# pc_sensything_v1_6.net
KiCad netlist of a schematic drawn in EAGLE
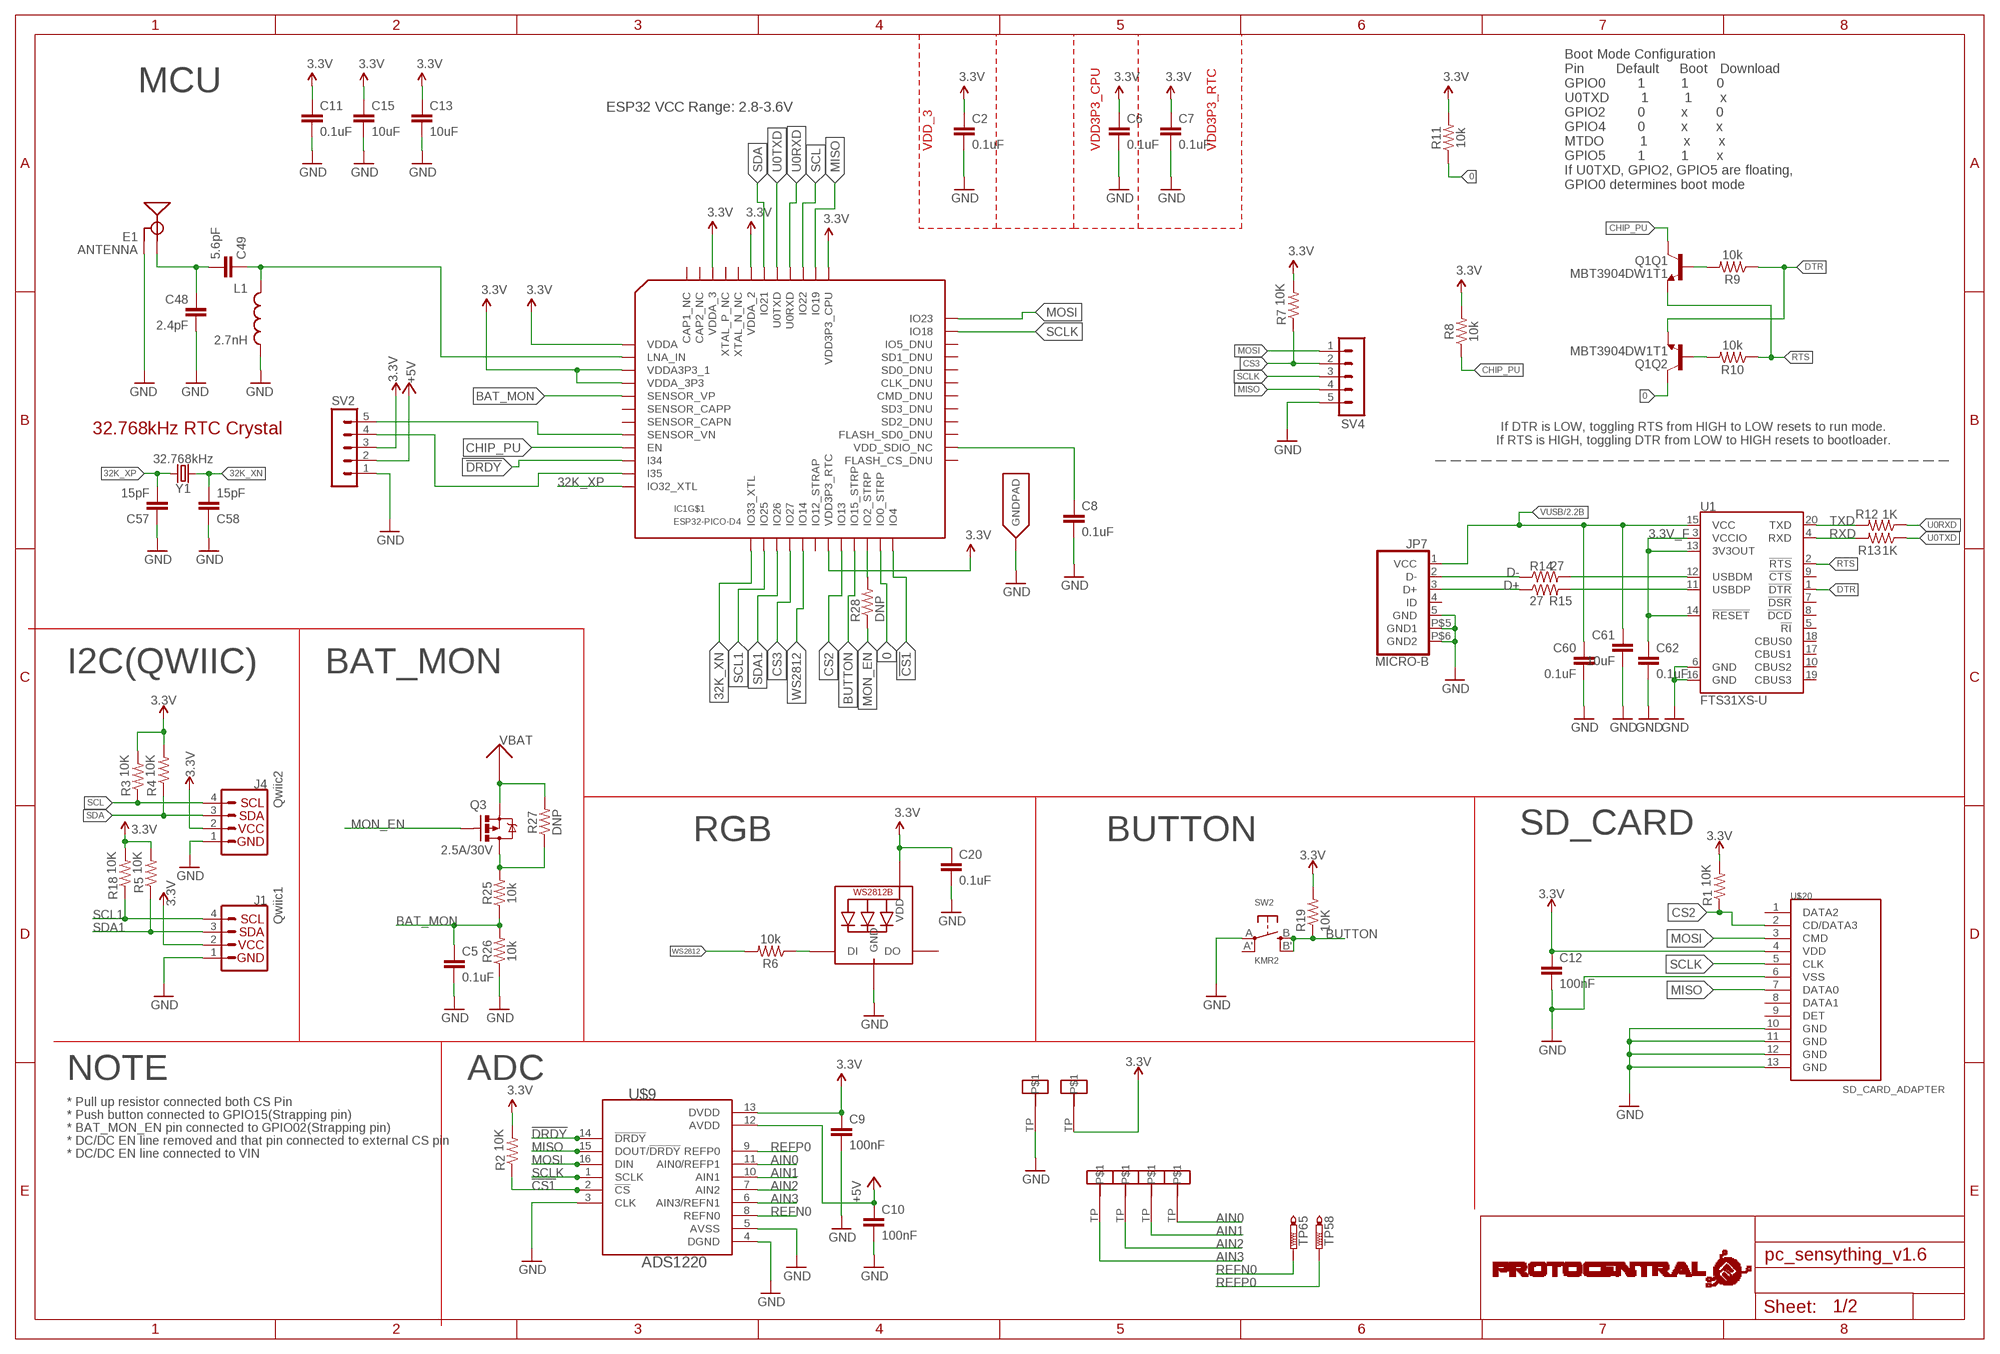
[diagram p0: schematic, sheet 1]
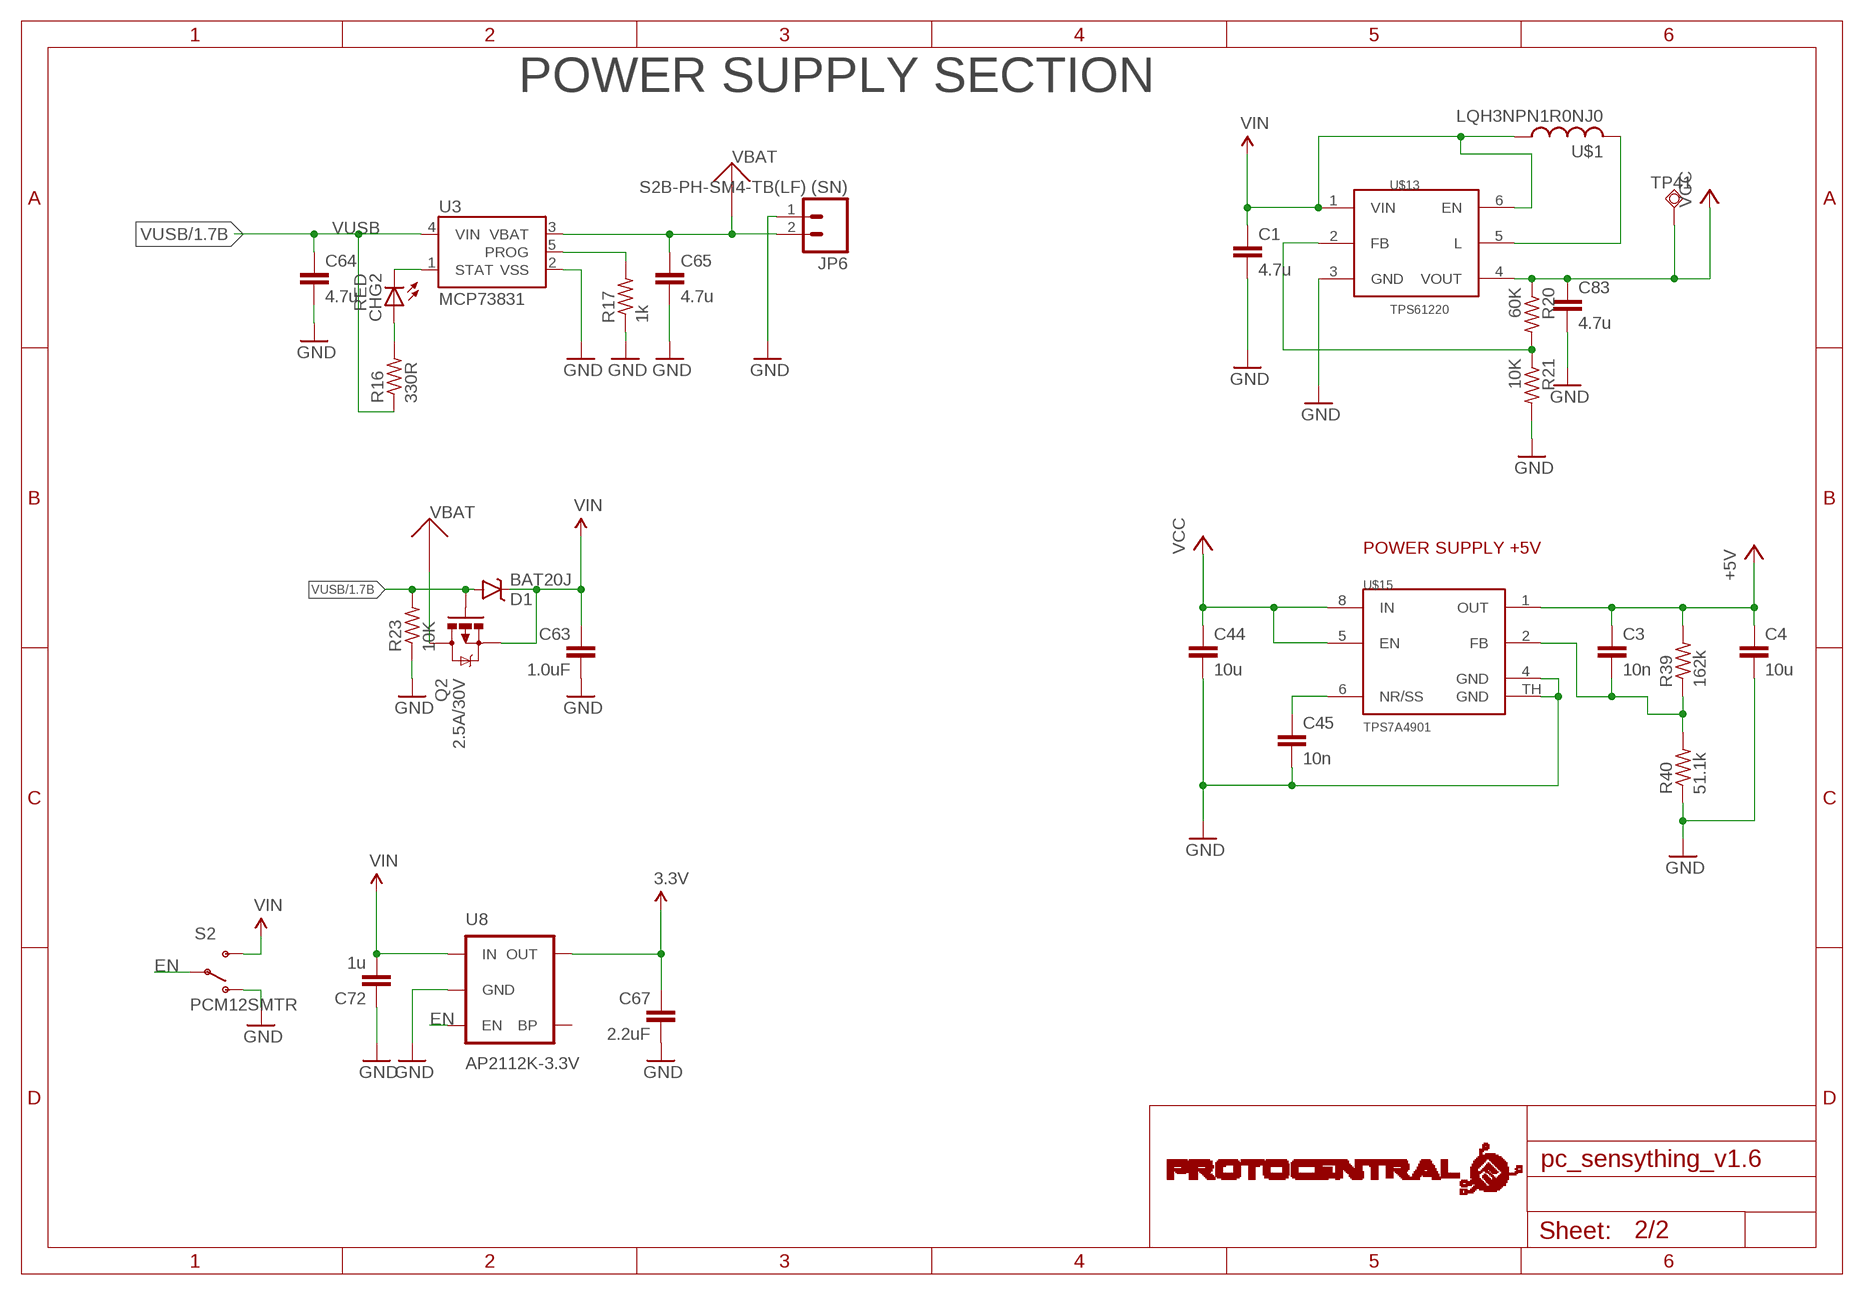
[diagram p1: schematic, sheet 2]

(export (version "E")
  (design (tool "Eeschema 10.0.6"))
  (components
    (comp (ref "C1")
      (value "4.7u")
      (footprint "eagle-import:C0805")
      (libsource (lib "eagle-import") (part "C-EUC0805"))
    )
    (comp (ref "C3")
      (value "10n")
      (footprint "eagle-import:C0402")
      (libsource (lib "eagle-import") (part "C-EUC0402"))
    )
    (comp (ref "C4")
      (value "10u")
      (footprint "eagle-import:C0805")
      (libsource (lib "eagle-import") (part "C-EUC0805"))
    )
    (comp (ref "C44")
      (value "10u")
      (footprint "eagle-import:C0805")
      (libsource (lib "eagle-import") (part "C-EUC0805"))
    )
    (comp (ref "C45")
      (value "10n")
      (footprint "eagle-import:C0402")
      (libsource (lib "eagle-import") (part "C-EUC0402"))
    )
    (comp (ref "C63")
      (value "1.0uF")
      (footprint "eagle-import:C0402")
      (libsource (lib "eagle-import") (part "C-EUC0402"))
    )
    (comp (ref "C64")
      (value "4.7u")
      (footprint "eagle-import:C0805")
      (libsource (lib "eagle-import") (part "C-EUC0805"))
    )
    (comp (ref "C65")
      (value "4.7u")
      (footprint "eagle-import:C0805")
      (libsource (lib "eagle-import") (part "C-EUC0805"))
    )
    (comp (ref "C67")
      (value "2.2uF")
      (footprint "eagle-import:C0402")
      (libsource (lib "eagle-import") (part "C-EUC0402"))
    )
    (comp (ref "C72")
      (value "1u")
      (footprint "eagle-import:C0402")
      (libsource (lib "eagle-import") (part "C-EUC0402"))
    )
    (comp (ref "C83")
      (value "4.7u")
      (footprint "eagle-import:C0805")
      (libsource (lib "eagle-import") (part "C-EUC0805"))
    )
    (comp (ref "CHG2")
      (value "RED")
      (footprint "eagle-import:CHIPLED_0603")
      (libsource (lib "eagle-import") (part "LEDCHIPLED_0603"))
    )
    (comp (ref "D1")
      (value "BAT20J")
      (footprint "eagle-import:SOD-323")
      (libsource (lib "eagle-import") (part "DIODE-SCHOTTKY-BAT20J"))
    )
    (comp (ref "JP6")
      (value "S2B-PH-SM4-TB(LF) (SN)")
      (footprint "eagle-import:JST-2-SMD")
      (libsource (lib "eagle-import") (part "M02-JST-2MM-SMT"))
    )
    (comp (ref "Q2")
      (value "2.5A/30V")
      (footprint "eagle-import:SOT23-3")
      (libsource (lib "eagle-import") (part "MOSFET-PCHANNELDMG2307L"))
    )
    (comp (ref "R16")
      (value "330R")
      (footprint "eagle-import:R0402")
      (libsource (lib "eagle-import") (part "R-US_R0402"))
    )
    (comp (ref "R17")
      (value "1k")
      (footprint "eagle-import:R0402")
      (libsource (lib "eagle-import") (part "R-US_R0402"))
    )
    (comp (ref "R20")
      (value "60K")
      (footprint "eagle-import:R0805")
      (libsource (lib "eagle-import") (part "R-US_R0805"))
    )
    (comp (ref "R21")
      (value "10K")
      (footprint "eagle-import:R0805")
      (libsource (lib "eagle-import") (part "R-US_R0805"))
    )
    (comp (ref "R23")
      (value "10K")
      (footprint "eagle-import:R0402")
      (libsource (lib "eagle-import") (part "R-US_R0402"))
    )
    (comp (ref "R39")
      (value "162k")
      (footprint "eagle-import:R0805")
      (libsource (lib "eagle-import") (part "R-US_R0805"))
    )
    (comp (ref "R40")
      (value "51.1k")
      (footprint "eagle-import:R0805")
      (libsource (lib "eagle-import") (part "R-US_R0805"))
    )
    (comp (ref "S2")
      (value "PCM12SMTR")
      (footprint "eagle-import:SWITCH-SPST-SMD-A")
      (libsource (lib "eagle-import") (part "SWITCH-SPDT-SMD-A"))
    )
    (comp (ref "TP41")
      (value "TPSQB1,27")
      (footprint "eagle-import:B1,27")
      (libsource (lib "eagle-import") (part "TPSQB1,27"))
    )
    (comp (ref "U$1")
      (value "LQH3NPN1R0NJ0")
      (footprint "eagle-import:LQH3NP")
      (libsource (lib "eagle-import") (part "LQH3NPN1R0NJ0"))
    )
    (comp (ref "U$5")
      (value "PROTY-LOGO")
      (footprint "eagle-import:LOGO-PROTY")
      (libsource (lib "eagle-import") (part "PROTY-LOGO"))
    )
    (comp (ref "U$13")
      (value "TPS61220")
      (footprint "eagle-import:SC-70-6")
      (libsource (lib "eagle-import") (part "TPS61222"))
    )
    (comp (ref "U$15")
      (value "TPS7A4901")
      (footprint "eagle-import:S-PDSO-G08")
      (libsource (lib "eagle-import") (part "TPS7A4901"))
    )
    (comp (ref "U3")
      (value "MCP73831")
      (footprint "eagle-import:SOT23-5")
      (libsource (lib "eagle-import") (part "MCP73831"))
    )
    (comp (ref "U8")
      (value "AP2112K-3.3V")
      (footprint "eagle-import:SOT23-5")
      (libsource (lib "eagle-import") (part "V_REG_LDOSMD"))
    )
    (comp (ref "C2")
      (value "0.1uF")
      (footprint "eagle-import:0402")
      (libsource (lib "eagle-import") (part "0.1UF-0402-16V-10%"))
    )
    (comp (ref "C5")
      (value "0.1uF")
      (footprint "eagle-import:0402")
      (libsource (lib "eagle-import") (part "0.1UF-0402-16V-10%"))
    )
    (comp (ref "C6")
      (value "0.1uF")
      (footprint "eagle-import:0402")
      (libsource (lib "eagle-import") (part "0.1UF-0402-16V-10%"))
    )
    (comp (ref "C7")
      (value "0.1uF")
      (footprint "eagle-import:0402")
      (libsource (lib "eagle-import") (part "0.1UF-0402-16V-10%"))
    )
    (comp (ref "C8")
      (value "0.1uF")
      (footprint "eagle-import:0402")
      (libsource (lib "eagle-import") (part "0.1UF-0402-16V-10%"))
    )
    (comp (ref "C9")
      (value "100nF")
      (footprint "eagle-import:C0805")
      (libsource (lib "eagle-import") (part "C-EUC0805"))
    )
    (comp (ref "C10")
      (value "100nF")
      (footprint "eagle-import:C0805")
      (libsource (lib "eagle-import") (part "C-EUC0805"))
    )
    (comp (ref "C11")
      (value "0.1uF")
      (footprint "eagle-import:0402")
      (libsource (lib "eagle-import") (part "0.1UF-0402-16V-10%"))
    )
    (comp (ref "C12")
      (value "100nF")
      (footprint "eagle-import:C0402")
      (libsource (lib "eagle-import") (part "C-EUC0402"))
    )
    (comp (ref "C13")
      (value "10uF")
      (footprint "eagle-import:0603")
      (libsource (lib "eagle-import") (part "10UF-0603-6.3V-20%"))
    )
    (comp (ref "C15")
      (value "10uF")
      (footprint "eagle-import:0603")
      (libsource (lib "eagle-import") (part "10UF-0603-6.3V-20%"))
    )
    (comp (ref "C20")
      (value "0.1uF")
      (footprint "eagle-import:0603")
      (libsource (lib "eagle-import") (part "0.1UF-0603-25V-(+80/-20%)"))
    )
    (comp (ref "C48")
      (value "2.4pF")
      (footprint "eagle-import:0603")
      (libsource (lib "eagle-import") (part "2.4PF-0603-50V-5%"))
    )
    (comp (ref "C49")
      (value "5.6pF")
      (footprint "eagle-import:0603")
      (libsource (lib "eagle-import") (part "5.6PF-50V-5%(0603)"))
    )
    (comp (ref "C57")
      (value "15pF")
      (footprint "eagle-import:0603")
      (libsource (lib "eagle-import") (part "15PF-0603-50V-5%"))
    )
    (comp (ref "C58")
      (value "15pF")
      (footprint "eagle-import:0603")
      (libsource (lib "eagle-import") (part "15PF-0603-50V-5%"))
    )
    (comp (ref "C60")
      (value "0.1uF")
      (footprint "eagle-import:C0402")
      (libsource (lib "eagle-import") (part "C-EUC0402"))
    )
    (comp (ref "C61")
      (value "10uF")
      (footprint "eagle-import:C0805")
      (libsource (lib "eagle-import") (part "C-EUC0805"))
    )
    (comp (ref "C62")
      (value "0.1uF")
      (footprint "eagle-import:C0402")
      (libsource (lib "eagle-import") (part "C-EUC0402"))
    )
    (comp (ref "E1")
      (value "ANTENNA")
      (footprint "eagle-import:TRACE_ANTENNA_2.4GHZ_25.7MM_TUNED")
      (libsource (lib "eagle-import") (part "ANTENNATRACE-TUNED"))
    )
    (comp (ref "IC1")
      (value "ESP32-PICO-D4")
      (footprint "eagle-import:QFN48")
      (libsource (lib "eagle-import") (part "CY8C29666_QFN48"))
    )
    (comp (ref "J1")
      (value "Qwiic1")
      (footprint "eagle-import:1X04_1MM_RA")
      (libsource (lib "eagle-import") (part "QWIIC_CONNECTORJS-1MM"))
    )
    (comp (ref "J4")
      (value "Qwiic2")
      (footprint "eagle-import:1X04_1MM_RA")
      (libsource (lib "eagle-import") (part "QWIIC_CONNECTORJS-1MM"))
    )
    (comp (ref "JP7")
      (value "MICRO-B")
      (footprint "eagle-import:MICRO-B")
      (libsource (lib "eagle-import") (part "MICRO-B"))
    )
    (comp (ref "L1")
      (value "2.7nH")
      (footprint "eagle-import:0603")
      (libsource (lib "eagle-import") (part "INDUCTOR0603"))
    )
    (comp (ref "LED1")
      (value "WS2812B5050")
      (footprint "eagle-import:WS2812B")
      (libsource (lib "eagle-import") (part "WS2812B5050"))
    )
    (comp (ref "Q1")
      (value "MBT3904DW1T1")
      (footprint "eagle-import:SC70-6")
      (libsource (lib "eagle-import") (part "MBT3904DW1T1"))
    )
    (comp (ref "Q3")
      (value "2.5A/30V")
      (footprint "eagle-import:SOT23-3")
      (libsource (lib "eagle-import") (part "MOSFET-PCHANNELDMG2307L"))
    )
    (comp (ref "R1")
      (value "10K")
      (footprint "eagle-import:R0402")
      (libsource (lib "eagle-import") (part "R-US_R0402"))
    )
    (comp (ref "R2")
      (value "10K")
      (footprint "eagle-import:R0402")
      (libsource (lib "eagle-import") (part "R-US_R0402"))
    )
    (comp (ref "R3")
      (value "10K")
      (footprint "eagle-import:R0402")
      (libsource (lib "eagle-import") (part "R-US_R0402"))
    )
    (comp (ref "R4")
      (value "10K")
      (footprint "eagle-import:R0402")
      (libsource (lib "eagle-import") (part "R-US_R0402"))
    )
    (comp (ref "R5")
      (value "10K")
      (footprint "eagle-import:R0402")
      (libsource (lib "eagle-import") (part "R-US_R0402"))
    )
    (comp (ref "R6")
      (value "10k")
      (footprint "eagle-import:0603")
      (libsource (lib "eagle-import") (part "10KOHM-1/10W-1%(0603)0603"))
    )
    (comp (ref "R7")
      (value "10K")
      (footprint "eagle-import:R0402")
      (libsource (lib "eagle-import") (part "R-US_R0402"))
    )
    (comp (ref "R8")
      (value "10k")
      (footprint "eagle-import:0603")
      (libsource (lib "eagle-import") (part "10KOHM-1/10W-1%(0603)0603"))
    )
    (comp (ref "R9")
      (value "10k")
      (footprint "eagle-import:0603")
      (libsource (lib "eagle-import") (part "10KOHM-0603-1/10W-1%"))
    )
    (comp (ref "R10")
      (value "10k")
      (footprint "eagle-import:0603")
      (libsource (lib "eagle-import") (part "10KOHM-0603-1/10W-1%"))
    )
    (comp (ref "R11")
      (value "10k")
      (footprint "eagle-import:0603")
      (libsource (lib "eagle-import") (part "10KOHM-1/10W-1%(0603)0603"))
    )
    (comp (ref "R12")
      (value "1K")
      (footprint "eagle-import:R0402")
      (libsource (lib "eagle-import") (part "R-US_R0402"))
    )
    (comp (ref "R13")
      (value "1K")
      (footprint "eagle-import:R0402")
      (libsource (lib "eagle-import") (part "R-US_R0402"))
    )
    (comp (ref "R14")
      (value "27")
      (footprint "eagle-import:R0402")
      (libsource (lib "eagle-import") (part "R-US_R0402"))
    )
    (comp (ref "R15")
      (value "27")
      (footprint "eagle-import:R0402")
      (libsource (lib "eagle-import") (part "R-US_R0402"))
    )
    (comp (ref "R18")
      (value "10K")
      (footprint "eagle-import:R0402")
      (libsource (lib "eagle-import") (part "R-US_R0402"))
    )
    (comp (ref "R19")
      (value "10K")
      (footprint "eagle-import:R0402")
      (libsource (lib "eagle-import") (part "R-US_R0402"))
    )
    (comp (ref "R25")
      (value "10k")
      (footprint "eagle-import:0603")
      (libsource (lib "eagle-import") (part "10KOHM-1/10W-1%(0603)0603"))
    )
    (comp (ref "R26")
      (value "10k")
      (footprint "eagle-import:0603")
      (libsource (lib "eagle-import") (part "10KOHM-1/10W-1%(0603)0603"))
    )
    (comp (ref "R27")
      (value "DNP")
      (footprint "eagle-import:0603")
      (libsource (lib "eagle-import") (part "10KOHM-1/10W-1%(0603)0603"))
    )
    (comp (ref "R28")
      (value "DNP")
      (footprint "eagle-import:R0402")
      (libsource (lib "eagle-import") (part "R-US_R0402"))
    )
    (comp (ref "SV2")
      (value "MA05-1")
      (footprint "eagle-import:MA05-1")
      (libsource (lib "eagle-import") (part "MA05-1"))
    )
    (comp (ref "SV4")
      (value "MA05-1")
      (footprint "eagle-import:MA05-1")
      (libsource (lib "eagle-import") (part "MA05-1"))
    )
    (comp (ref "SW2")
      (value "KMR2")
      (footprint "eagle-import:BTN_KMR2_4.6X2.8")
      (libsource (lib "eagle-import") (part "SWITCH_TACT_SMT4.6X2.8"))
    )
    (comp (ref "TP58")
      (value "PTR1PAD1-13")
      (footprint "eagle-import:P1-13")
      (libsource (lib "eagle-import") (part "PTR1PAD1-13"))
    )
    (comp (ref "TP65")
      (value "PTR1PAD1-13")
      (footprint "eagle-import:P1-13")
      (libsource (lib "eagle-import") (part "PTR1PAD1-13"))
    )
    (comp (ref "U$3")
      (value "SENSYTHING_CON")
      (footprint "eagle-import:SENSYTHING_CON")
      (libsource (lib "eagle-import") (part "SENSYTHING_CON"))
    )
    (comp (ref "U$7")
      (value "SENSYTHING_CON")
      (footprint "eagle-import:SENSYTHING_CON")
      (libsource (lib "eagle-import") (part "SENSYTHING_CON"))
    )
    (comp (ref "U$8")
      (value "SENSYTHING_CON")
      (footprint "eagle-import:SENSYTHING_CON")
      (libsource (lib "eagle-import") (part "SENSYTHING_CON"))
    )
    (comp (ref "U$9")
      (value "ADS1220")
      (footprint "eagle-import:TSSOP-16")
      (libsource (lib "eagle-import") (part "ADS1220"))
    )
    (comp (ref "U$11")
      (value "SENSYTHING_CON")
      (footprint "eagle-import:SENSYTHING_CON")
      (libsource (lib "eagle-import") (part "SENSYTHING_CON"))
    )
    (comp (ref "U$12")
      (value "SENSYTHING_CON")
      (footprint "eagle-import:SENSYTHING_CON")
      (libsource (lib "eagle-import") (part "SENSYTHING_CON"))
    )
    (comp (ref "U$14")
      (value "SENSYTHING_CON")
      (footprint "eagle-import:SENSYTHING_CON")
      (libsource (lib "eagle-import") (part "SENSYTHING_CON"))
    )
    (comp (ref "U$19")
      (value "PROTY-LOGO")
      (footprint "eagle-import:LOGO-PROTY")
      (libsource (lib "eagle-import") (part "PROTY-LOGO"))
    )
    (comp (ref "U$20")
      (value "SD_CARD_ADAPTER")
      (footprint "eagle-import:SD-105162")
      (libsource (lib "eagle-import") (part "SD_CARD_ADAPTER"))
    )
    (comp (ref "U1")
      (value "FTS31XS-U")
      (footprint "eagle-import:SSOP20_L")
      (libsource (lib "eagle-import") (part "FT231XS"))
    )
    (comp (ref "Y1")
      (value "32.768kHz")
      (footprint "eagle-import:CRYSTAL-SMD-3.2X1.5MM")
      (libsource (lib "eagle-import") (part "CRYSTAL-32.768KHZSMD-3.2X1.5"))
    )
  )
  (nets
    (net (code "1") (name "+5V") (class "Default")
      (node (ref "C10") (pin "1") (pinfunction "1_1") (pintype "passive"))
      (node (ref "C3") (pin "1") (pinfunction "1_1") (pintype "passive"))
      (node (ref "C4") (pin "1") (pinfunction "1_1") (pintype "passive"))
      (node (ref "R39") (pin "2") (pinfunction "2_2") (pintype "passive"))
      (node (ref "SV2") (pin "2") (pinfunction "2_2") (pintype "passive"))
      (node (ref "U$15") (pin "1") (pinfunction "OUT_1") (pintype "bidirectional"))
      (node (ref "U$9") (pin "12") (pinfunction "AVDD_12") (pintype "bidirectional"))
    )
    (net (code "2") (name "0") (class "Default")
      (node (ref "IC1") (pin "23") (pinfunction "IO0_STRP_23") (pintype "bidirectional"))
      (node (ref "Q1") (pin "6") (pinfunction "C_6") (pintype "passive"))
      (node (ref "R11") (pin "1") (pinfunction "1_1") (pintype "passive"))
    )
    (net (code "3") (name "3.3V") (class "Default")
      (node (ref "C11") (pin "1") (pinfunction "1_1") (pintype "passive"))
      (node (ref "C12") (pin "1") (pinfunction "1_1") (pintype "passive"))
      (node (ref "C13") (pin "1") (pinfunction "1_1") (pintype "passive"))
      (node (ref "C15") (pin "1") (pinfunction "1_1") (pintype "passive"))
      (node (ref "C2") (pin "1") (pinfunction "1_1") (pintype "passive"))
      (node (ref "C20") (pin "1") (pinfunction "1_1") (pintype "passive"))
      (node (ref "C6") (pin "1") (pinfunction "1_1") (pintype "passive"))
      (node (ref "C67") (pin "1") (pinfunction "1_1") (pintype "passive"))
      (node (ref "C7") (pin "1") (pinfunction "1_1") (pintype "passive"))
      (node (ref "C9") (pin "1") (pinfunction "1_1") (pintype "passive"))
      (node (ref "IC1") (pin "1") (pinfunction "VDDA_1") (pintype "bidirectional"))
      (node (ref "IC1") (pin "19") (pinfunction "VDD3P3_RTC_19") (pintype "bidirectional"))
      (node (ref "IC1") (pin "3") (pinfunction "VDDA3P3_1_3") (pintype "bidirectional"))
      (node (ref "IC1") (pin "37") (pinfunction "VDD3P3_CPU_37") (pintype "bidirectional"))
      (node (ref "IC1") (pin "4") (pinfunction "VDDA_3P3_4") (pintype "bidirectional"))
      (node (ref "IC1") (pin "43") (pinfunction "VDDA_2_43") (pintype "bidirectional"))
      (node (ref "IC1") (pin "46") (pinfunction "VDDA_3_46") (pintype "bidirectional"))
      (node (ref "J1") (pin "2") (pinfunction "2_2") (pintype "power_in"))
      (node (ref "J4") (pin "2") (pinfunction "2_2") (pintype "power_in"))
      (node (ref "LED1") (pin "1-VDD") (pinfunction "VDD_1-VDD") (pintype "power_in"))
      (node (ref "R1") (pin "2") (pinfunction "2_2") (pintype "passive"))
      (node (ref "R11") (pin "2") (pinfunction "2_2") (pintype "passive"))
      (node (ref "R18") (pin "2") (pinfunction "2_2") (pintype "passive"))
      (node (ref "R19") (pin "2") (pinfunction "2_2") (pintype "passive"))
      (node (ref "R2") (pin "2") (pinfunction "2_2") (pintype "passive"))
      (node (ref "R3") (pin "2") (pinfunction "2_2") (pintype "passive"))
      (node (ref "R4") (pin "2") (pinfunction "2_2") (pintype "passive"))
      (node (ref "R5") (pin "2") (pinfunction "2_2") (pintype "passive"))
      (node (ref "R7") (pin "2") (pinfunction "2_2") (pintype "passive"))
      (node (ref "R8") (pin "2") (pinfunction "2_2") (pintype "passive"))
      (node (ref "SV2") (pin "3") (pinfunction "3_3") (pintype "passive"))
      (node (ref "U$14") (pin "TP") (pinfunction "P$1_TP") (pintype "bidirectional"))
      (node (ref "U$20") (pin "4") (pinfunction "VDD_4") (pintype "bidirectional"))
      (node (ref "U$9") (pin "13") (pinfunction "DVDD_13") (pintype "bidirectional"))
      (node (ref "U8") (pin "5") (pinfunction "OUT_5") (pintype "passive"))
    )
    (net (code "4") (name "3.3V_F") (class "Default")
      (node (ref "C62") (pin "1") (pinfunction "1_1") (pintype "passive"))
      (node (ref "U1") (pin "13") (pinfunction "3V3OUT_13") (pintype "bidirectional"))
      (node (ref "U1") (pin "14") (pinfunction "~{RESET}_14") (pintype "bidirectional"))
      (node (ref "U1") (pin "3") (pinfunction "VCCIO_3") (pintype "bidirectional"))
    )
    (net (code "5") (name "32K_XN") (class "Default")
      (node (ref "C58") (pin "2") (pinfunction "2_2") (pintype "passive"))
      (node (ref "IC1") (pin "13") (pinfunction "IO33_XTL_13") (pintype "bidirectional"))
      (node (ref "Y1") (pin "P$2") (pinfunction "2_P$2") (pintype "passive"))
    )
    (net (code "6") (name "32K_XP") (class "Default")
      (node (ref "C57") (pin "2") (pinfunction "2_2") (pintype "passive"))
      (node (ref "IC1") (pin "12") (pinfunction "IO32_XTL_12") (pintype "bidirectional"))
      (node (ref "Y1") (pin "P$1") (pinfunction "1_P$1") (pintype "passive"))
    )
    (net (code "7") (name "AIN0") (class "Default")
      (node (ref "U$11") (pin "TP") (pinfunction "P$1_TP") (pintype "bidirectional"))
      (node (ref "U$9") (pin "11") (pinfunction "AIN0/REFP1_11") (pintype "bidirectional"))
    )
    (net (code "8") (name "AIN1") (class "Default")
      (node (ref "U$8") (pin "TP") (pinfunction "P$1_TP") (pintype "bidirectional"))
      (node (ref "U$9") (pin "10") (pinfunction "AIN1_10") (pintype "bidirectional"))
    )
    (net (code "9") (name "AIN2") (class "Default")
      (node (ref "U$7") (pin "TP") (pinfunction "P$1_TP") (pintype "bidirectional"))
      (node (ref "U$9") (pin "7") (pinfunction "AIN2_7") (pintype "bidirectional"))
    )
    (net (code "10") (name "AIN3") (class "Default")
      (node (ref "U$3") (pin "TP") (pinfunction "P$1_TP") (pintype "bidirectional"))
      (node (ref "U$9") (pin "6") (pinfunction "AIN3/REFN1_6") (pintype "bidirectional"))
    )
    (net (code "11") (name "BAT_MON") (class "Default")
      (node (ref "C5") (pin "1") (pinfunction "1_1") (pintype "passive"))
      (node (ref "IC1") (pin "5") (pinfunction "SENSOR_VP_5") (pintype "bidirectional"))
      (node (ref "R25") (pin "1") (pinfunction "1_1") (pintype "passive"))
      (node (ref "R26") (pin "2") (pinfunction "2_2") (pintype "passive"))
    )
    (net (code "12") (name "BUTTON") (class "Default")
      (node (ref "IC1") (pin "21") (pinfunction "IO15_STRP_21") (pintype "bidirectional"))
      (node (ref "R19") (pin "1") (pinfunction "1_1") (pintype "passive"))
      (node (ref "SW2") (pin "B") (pinfunction "S_B") (pintype "passive"))
      (node (ref "SW2") (pin "B'") (pinfunction "S1_B'") (pintype "passive"))
    )
    (net (code "13") (name "CHIP_PU") (class "Default")
      (node (ref "IC1") (pin "9") (pinfunction "EN_9") (pintype "bidirectional"))
      (node (ref "Q1") (pin "3") (pinfunction "C_3") (pintype "passive"))
      (node (ref "R8") (pin "1") (pinfunction "1_1") (pintype "passive"))
    )
    (net (code "14") (name "CS2") (class "Default")
      (node (ref "IC1") (pin "20") (pinfunction "IO13_20") (pintype "bidirectional"))
      (node (ref "R1") (pin "1") (pinfunction "1_1") (pintype "passive"))
      (node (ref "U$20") (pin "2") (pinfunction "CD/DATA3_2") (pintype "bidirectional"))
    )
    (net (code "15") (name "CS3") (class "Default")
      (node (ref "IC1") (pin "16") (pinfunction "IO27_16") (pintype "bidirectional"))
      (node (ref "R7") (pin "1") (pinfunction "1_1") (pintype "passive"))
      (node (ref "SV4") (pin "2") (pinfunction "2_2") (pintype "passive"))
    )
    (net (code "16") (name "D+") (class "Default")
      (node (ref "JP7") (pin "3") (pinfunction "D+_3") (pintype "bidirectional"))
      (node (ref "R15") (pin "1") (pinfunction "1_1") (pintype "passive"))
    )
    (net (code "17") (name "D-") (class "Default")
      (node (ref "JP7") (pin "2") (pinfunction "D-_2") (pintype "bidirectional"))
      (node (ref "R14") (pin "1") (pinfunction "1_1") (pintype "passive"))
    )
    (net (code "18") (name "DTR") (class "Default")
      (node (ref "Q1") (pin "1") (pinfunction "E_1") (pintype "passive"))
      (node (ref "R9") (pin "1") (pinfunction "1_1") (pintype "passive"))
      (node (ref "U1") (pin "1") (pinfunction "~{DTR}_1") (pintype "bidirectional"))
    )
    (net (code "19") (name "EN") (class "Default")
      (node (ref "S2") (pin "2") (pinfunction "P_2") (pintype "passive"))
      (node (ref "U8") (pin "3") (pinfunction "EN_3") (pintype "input"))
    )
    (net (code "20") (name "GND") (class "Default")
      (node (ref "C1") (pin "2") (pinfunction "2_2") (pintype "passive"))
      (node (ref "C10") (pin "2") (pinfunction "2_2") (pintype "passive"))
      (node (ref "C11") (pin "2") (pinfunction "2_2") (pintype "passive"))
      (node (ref "C12") (pin "2") (pinfunction "2_2") (pintype "passive"))
      (node (ref "C13") (pin "2") (pinfunction "2_2") (pintype "passive"))
      (node (ref "C15") (pin "2") (pinfunction "2_2") (pintype "passive"))
      (node (ref "C2") (pin "2") (pinfunction "2_2") (pintype "passive"))
      (node (ref "C20") (pin "2") (pinfunction "2_2") (pintype "passive"))
      (node (ref "C4") (pin "2") (pinfunction "2_2") (pintype "passive"))
      (node (ref "C44") (pin "2") (pinfunction "2_2") (pintype "passive"))
      (node (ref "C45") (pin "2") (pinfunction "2_2") (pintype "passive"))
      (node (ref "C48") (pin "2") (pinfunction "2_2") (pintype "passive"))
      (node (ref "C5") (pin "2") (pinfunction "2_2") (pintype "passive"))
      (node (ref "C57") (pin "1") (pinfunction "1_1") (pintype "passive"))
      (node (ref "C58") (pin "1") (pinfunction "1_1") (pintype "passive"))
      (node (ref "C6") (pin "2") (pinfunction "2_2") (pintype "passive"))
      (node (ref "C60") (pin "2") (pinfunction "2_2") (pintype "passive"))
      (node (ref "C61") (pin "2") (pinfunction "2_2") (pintype "passive"))
      (node (ref "C62") (pin "2") (pinfunction "2_2") (pintype "passive"))
      (node (ref "C63") (pin "2") (pinfunction "2_2") (pintype "passive"))
      (node (ref "C64") (pin "2") (pinfunction "2_2") (pintype "passive"))
      (node (ref "C65") (pin "2") (pinfunction "2_2") (pintype "passive"))
      (node (ref "C67") (pin "2") (pinfunction "2_2") (pintype "passive"))
      (node (ref "C7") (pin "2") (pinfunction "2_2") (pintype "passive"))
      (node (ref "C72") (pin "1") (pinfunction "1_1") (pintype "passive"))
      (node (ref "C8") (pin "2") (pinfunction "2_2") (pintype "passive"))
      (node (ref "C83") (pin "2") (pinfunction "2_2") (pintype "passive"))
      (node (ref "C9") (pin "2") (pinfunction "2_2") (pintype "passive"))
      (node (ref "E1") (pin "GND") (pinfunction "GND_GND") (pintype "bidirectional"))
      (node (ref "E1") (pin "GND2") (pinfunction "GND_GND2") (pintype "bidirectional"))
      (node (ref "IC1") (pin "EXP") (pinfunction "GNDPAD_EXP") (pintype "power_in"))
      (node (ref "J1") (pin "1") (pinfunction "1_1") (pintype "power_in"))
      (node (ref "J4") (pin "1") (pinfunction "1_1") (pintype "power_in"))
      (node (ref "JP6") (pin "1") (pinfunction "1_1") (pintype "passive"))
      (node (ref "JP7") (pin "5") (pinfunction "GND_5") (pintype "bidirectional"))
      (node (ref "JP7") (pin "P$5") (pinfunction "GND1_P$5") (pintype "bidirectional"))
      (node (ref "JP7") (pin "P$6") (pinfunction "GND2_P$6") (pintype "bidirectional"))
      (node (ref "L1") (pin "2") (pinfunction "2_2") (pintype "passive"))
      (node (ref "LED1") (pin "3-GND") (pinfunction "GND_3-GND") (pintype "power_in"))
      (node (ref "R17") (pin "1") (pinfunction "1_1") (pintype "passive"))
      (node (ref "R21") (pin "2") (pinfunction "2_2") (pintype "passive"))
      (node (ref "R23") (pin "1") (pinfunction "1_1") (pintype "passive"))
      (node (ref "R26") (pin "1") (pinfunction "1_1") (pintype "passive"))
      (node (ref "R40") (pin "1") (pinfunction "1_1") (pintype "passive"))
      (node (ref "S2") (pin "1") (pinfunction "O_1") (pintype "passive"))
      (node (ref "SV2") (pin "1") (pinfunction "1_1") (pintype "passive"))
      (node (ref "SV4") (pin "5") (pinfunction "5_5") (pintype "passive"))
      (node (ref "SW2") (pin "A") (pinfunction "P_A") (pintype "passive"))
      (node (ref "U$12") (pin "TP") (pinfunction "P$1_TP") (pintype "bidirectional"))
      (node (ref "U$13") (pin "3") (pinfunction "GND_3") (pintype "bidirectional"))
      (node (ref "U$15") (pin "4") (pinfunction "GND_4") (pintype "bidirectional"))
      (node (ref "U$15") (pin "TH") (pinfunction "GND_TH") (pintype "bidirectional"))
      (node (ref "U$20") (pin "10") (pinfunction "GND_10") (pintype "bidirectional"))
      (node (ref "U$20") (pin "11") (pinfunction "GND_11") (pintype "bidirectional"))
      (node (ref "U$20") (pin "12") (pinfunction "GND_12") (pintype "bidirectional"))
      (node (ref "U$20") (pin "13") (pinfunction "GND_13") (pintype "bidirectional"))
      (node (ref "U$20") (pin "6") (pinfunction "VSS_6") (pintype "bidirectional"))
      (node (ref "U$9") (pin "3") (pinfunction "CLK_3") (pintype "bidirectional"))
      (node (ref "U$9") (pin "4") (pinfunction "DGND_4") (pintype "bidirectional"))
      (node (ref "U$9") (pin "5") (pinfunction "AVSS_5") (pintype "bidirectional"))
      (node (ref "U1") (pin "16") (pinfunction "GND_16") (pintype "bidirectional"))
      (node (ref "U1") (pin "6") (pinfunction "GND_6") (pintype "bidirectional"))
      (node (ref "U3") (pin "2") (pinfunction "VSS_2") (pintype "power_in"))
      (node (ref "U8") (pin "2") (pinfunction "GND_2") (pintype "input"))
    )
    (net (code "21") (name "IO12_STRAP") (class "Default")
      (node (ref "IC1") (pin "18") (pinfunction "IO12_STRAP_18") (pintype "power_in"))
    )
    (net (code "22") (name "MISO") (class "Default")
      (node (ref "IC1") (pin "38") (pinfunction "IO19_38") (pintype "bidirectional"))
      (node (ref "SV4") (pin "4") (pinfunction "4_4") (pintype "passive"))
      (node (ref "U$20") (pin "7") (pinfunction "DATA0_7") (pintype "bidirectional"))
      (node (ref "U$9") (pin "15") (pinfunction "DOUT/~{DRDY}_15") (pintype "bidirectional"))
    )
    (net (code "23") (name "MON_EN") (class "Default")
      (node (ref "Q3") (pin "1") (pinfunction "G_1") (pintype "passive"))
      (node (ref "R28") (pin "1") (pinfunction "1_1") (pintype "passive"))
    )
    (net (code "24") (name "MOSI") (class "Default")
      (node (ref "IC1") (pin "36") (pinfunction "IO23_36") (pintype "bidirectional"))
      (node (ref "SV4") (pin "1") (pinfunction "1_1") (pintype "passive"))
      (node (ref "U$20") (pin "3") (pinfunction "CMD_3") (pintype "bidirectional"))
      (node (ref "U$9") (pin "16") (pinfunction "DIN_16") (pintype "bidirectional"))
    )
    (net (code "25") (name "Net-(CHG2-PadA)") (class "Default")
      (node (ref "CHG2") (pin "A") (pinfunction "A_A") (pintype "passive"))
      (node (ref "R16") (pin "2") (pinfunction "2_2") (pintype "passive"))
    )
    (net (code "26") (name "Net-(E1-SIGNAL)") (class "Default")
      (node (ref "C48") (pin "1") (pinfunction "1_1") (pintype "passive"))
      (node (ref "C49") (pin "2") (pinfunction "2_2") (pintype "passive"))
      (node (ref "E1") (pin "ANT") (pinfunction "SIGNAL_ANT") (pintype "bidirectional"))
    )
    (net (code "27") (name "Net-(IC1A-I35)") (class "Default")
      (node (ref "IC1") (pin "11") (pinfunction "I35_11") (pintype "bidirectional"))
      (node (ref "SV2") (pin "4") (pinfunction "4_4") (pintype "passive"))
    )
    (net (code "28") (name "Net-(IC1A-IO2_STRP)") (class "Default")
      (node (ref "IC1") (pin "22") (pinfunction "IO2_STRP_22") (pintype "bidirectional"))
      (node (ref "R28") (pin "2") (pinfunction "2_2") (pintype "passive"))
    )
    (net (code "29") (name "Net-(IC1A-LNA_IN)") (class "Default")
      (node (ref "C49") (pin "1") (pinfunction "1_1") (pintype "passive"))
      (node (ref "IC1") (pin "2") (pinfunction "LNA_IN_2") (pintype "bidirectional"))
      (node (ref "L1") (pin "1") (pinfunction "1_1") (pintype "passive"))
    )
    (net (code "30") (name "Net-(IC1A-SENSOR_VN)") (class "Default")
      (node (ref "IC1") (pin "8") (pinfunction "SENSOR_VN_8") (pintype "bidirectional"))
      (node (ref "SV2") (pin "5") (pinfunction "5_5") (pintype "passive"))
    )
    (net (code "31") (name "Net-(IC1A-VDD_SDIO_NC)") (class "Default")
      (node (ref "C8") (pin "1") (pinfunction "1_1") (pintype "passive"))
      (node (ref "IC1") (pin "26") (pinfunction "VDD_SDIO_NC_26") (pintype "bidirectional"))
    )
    (net (code "32") (name "Net-(LED1-DI)") (class "Default")
      (node (ref "LED1") (pin "4-DIN") (pinfunction "DI_4-DIN") (pintype "input"))
      (node (ref "R6") (pin "1") (pinfunction "1_1") (pintype "passive"))
    )
    (net (code "33") (name "Net-(Q1A-B)") (class "Default")
      (node (ref "Q1") (pin "5") (pinfunction "B_5") (pintype "passive"))
      (node (ref "R9") (pin "2") (pinfunction "2_2") (pintype "passive"))
    )
    (net (code "34") (name "Net-(Q1B-B)") (class "Default")
      (node (ref "Q1") (pin "2") (pinfunction "B_2") (pintype "passive"))
      (node (ref "R10") (pin "2") (pinfunction "2_2") (pintype "passive"))
    )
    (net (code "35") (name "Net-(Q3-D)") (class "Default")
      (node (ref "Q3") (pin "3") (pinfunction "D_3") (pintype "passive"))
      (node (ref "R25") (pin "2") (pinfunction "2_2") (pintype "passive"))
      (node (ref "R27") (pin "1") (pinfunction "1_1") (pintype "passive"))
    )
    (net (code "36") (name "Net-(U$1-2)") (class "Default")
      (node (ref "U$1") (pin "P$2") (pinfunction "2_P$2") (pintype "passive"))
      (node (ref "U$13") (pin "5") (pinfunction "L_5") (pintype "bidirectional"))
    )
    (net (code "37") (name "Net-(U$13-FB)") (class "Default")
      (node (ref "R20") (pin "2") (pinfunction "2_2") (pintype "passive"))
      (node (ref "R21") (pin "1") (pinfunction "1_1") (pintype "passive"))
      (node (ref "U$13") (pin "2") (pinfunction "FB_2") (pintype "bidirectional"))
    )
    (net (code "38") (name "Net-(U$15-FB)") (class "Default")
      (node (ref "C3") (pin "2") (pinfunction "2_2") (pintype "passive"))
      (node (ref "R39") (pin "1") (pinfunction "1_1") (pintype "passive"))
      (node (ref "R40") (pin "2") (pinfunction "2_2") (pintype "passive"))
      (node (ref "U$15") (pin "2") (pinfunction "FB_2") (pintype "bidirectional"))
    )
    (net (code "39") (name "Net-(U$15-NR{slash}SS)") (class "Default")
      (node (ref "C45") (pin "1") (pinfunction "1_1") (pintype "passive"))
      (node (ref "U$15") (pin "6") (pinfunction "NR/SS_6") (pintype "bidirectional"))
    )
    (net (code "40") (name "Net-(U1-USBDM)") (class "Default")
      (node (ref "R14") (pin "2") (pinfunction "2_2") (pintype "passive"))
      (node (ref "U1") (pin "12") (pinfunction "USBDM_12") (pintype "bidirectional"))
    )
    (net (code "41") (name "Net-(U1-USBDP)") (class "Default")
      (node (ref "R15") (pin "2") (pinfunction "2_2") (pintype "passive"))
      (node (ref "U1") (pin "11") (pinfunction "USBDP_11") (pintype "bidirectional"))
    )
    (net (code "42") (name "Net-(U3-PROG)") (class "Default")
      (node (ref "R17") (pin "2") (pinfunction "2_2") (pintype "passive"))
      (node (ref "U3") (pin "5") (pinfunction "PROG_5") (pintype "input"))
    )
    (net (code "43") (name "Net-(U3-STAT)") (class "Default")
      (node (ref "CHG2") (pin "C") (pinfunction "C_C") (pintype "passive"))
      (node (ref "U3") (pin "1") (pinfunction "STAT_1") (pintype "output"))
    )
    (net (code "44") (name "REFN0") (class "Default")
      (node (ref "TP65") (pin "TP") (pinfunction "TP_TP") (pintype "input"))
      (node (ref "U$9") (pin "8") (pinfunction "REFN0_8") (pintype "bidirectional"))
    )
    (net (code "45") (name "REFP0") (class "Default")
      (node (ref "TP58") (pin "TP") (pinfunction "TP_TP") (pintype "input"))
      (node (ref "U$9") (pin "9") (pinfunction "REFP0_9") (pintype "bidirectional"))
    )
    (net (code "46") (name "RTS") (class "Default")
      (node (ref "Q1") (pin "4") (pinfunction "E_4") (pintype "passive"))
      (node (ref "R10") (pin "1") (pinfunction "1_1") (pintype "passive"))
      (node (ref "U1") (pin "2") (pinfunction "~{RTS}_2") (pintype "bidirectional"))
    )
    (net (code "47") (name "RXD") (class "Default")
      (node (ref "R13") (pin "2") (pinfunction "2_2") (pintype "passive"))
      (node (ref "U1") (pin "4") (pinfunction "RXD_4") (pintype "bidirectional"))
    )
    (net (code "48") (name "SCL") (class "Default")
      (node (ref "IC1") (pin "39") (pinfunction "IO22_39") (pintype "bidirectional"))
      (node (ref "J4") (pin "4") (pinfunction "4_4") (pintype "passive"))
      (node (ref "R3") (pin "1") (pinfunction "1_1") (pintype "passive"))
    )
    (net (code "49") (name "SCL1") (class "Default")
      (node (ref "IC1") (pin "14") (pinfunction "IO25_14") (pintype "bidirectional"))
      (node (ref "J1") (pin "4") (pinfunction "4_4") (pintype "passive"))
      (node (ref "R18") (pin "1") (pinfunction "1_1") (pintype "passive"))
    )
    (net (code "50") (name "SCLK") (class "Default")
      (node (ref "IC1") (pin "35") (pinfunction "IO18_35") (pintype "bidirectional"))
      (node (ref "SV4") (pin "3") (pinfunction "3_3") (pintype "passive"))
      (node (ref "U$20") (pin "5") (pinfunction "CLK_5") (pintype "bidirectional"))
      (node (ref "U$9") (pin "1") (pinfunction "SCLK_1") (pintype "bidirectional"))
    )
    (net (code "51") (name "SDA") (class "Default")
      (node (ref "IC1") (pin "42") (pinfunction "IO21_42") (pintype "power_in"))
      (node (ref "J4") (pin "3") (pinfunction "3_3") (pintype "passive"))
      (node (ref "R4") (pin "1") (pinfunction "1_1") (pintype "passive"))
    )
    (net (code "52") (name "SDA1") (class "Default")
      (node (ref "IC1") (pin "15") (pinfunction "IO26_15") (pintype "bidirectional"))
      (node (ref "J1") (pin "3") (pinfunction "3_3") (pintype "passive"))
      (node (ref "R5") (pin "1") (pinfunction "1_1") (pintype "passive"))
    )
    (net (code "53") (name "SENSOR_CAPN") (class "Default")
      (node (ref "IC1") (pin "7") (pinfunction "SENSOR_CAPN_7") (pintype "power_in"))
    )
    (net (code "54") (name "TXD") (class "Default")
      (node (ref "R12") (pin "2") (pinfunction "2_2") (pintype "passive"))
      (node (ref "U1") (pin "20") (pinfunction "TXD_20") (pintype "bidirectional"))
    )
    (net (code "55") (name "U0RXD") (class "Default")
      (node (ref "IC1") (pin "40") (pinfunction "U0RXD_40") (pintype "bidirectional"))
      (node (ref "R12") (pin "1") (pinfunction "1_1") (pintype "passive"))
    )
    (net (code "56") (name "U0TXD") (class "Default")
      (node (ref "IC1") (pin "41") (pinfunction "U0TXD_41") (pintype "bidirectional"))
      (node (ref "R13") (pin "1") (pinfunction "1_1") (pintype "passive"))
    )
    (net (code "57") (name "VBAT") (class "Default")
      (node (ref "C65") (pin "1") (pinfunction "1_1") (pintype "passive"))
      (node (ref "JP6") (pin "2") (pinfunction "2_2") (pintype "passive"))
      (node (ref "Q2") (pin "3") (pinfunction "D_3") (pintype "passive"))
      (node (ref "Q3") (pin "2") (pinfunction "S_2") (pintype "passive"))
      (node (ref "R27") (pin "2") (pinfunction "2_2") (pintype "passive"))
      (node (ref "U3") (pin "3") (pinfunction "VBAT_3") (pintype "power_in"))
    )
    (net (code "58") (name "VCC") (class "Default")
      (node (ref "C44") (pin "1") (pinfunction "1_1") (pintype "passive"))
      (node (ref "C83") (pin "1") (pinfunction "1_1") (pintype "passive"))
      (node (ref "R20") (pin "1") (pinfunction "1_1") (pintype "passive"))
      (node (ref "TP41") (pin "TP") (pinfunction "TP_TP") (pintype "input"))
      (node (ref "U$13") (pin "4") (pinfunction "VOUT_4") (pintype "bidirectional"))
      (node (ref "U$15") (pin "5") (pinfunction "EN_5") (pintype "bidirectional"))
      (node (ref "U$15") (pin "8") (pinfunction "IN_8") (pintype "bidirectional"))
    )
    (net (code "59") (name "VIN") (class "Default")
      (node (ref "C1") (pin "1") (pinfunction "1_1") (pintype "passive"))
      (node (ref "C63") (pin "1") (pinfunction "1_1") (pintype "passive"))
      (node (ref "C72") (pin "2") (pinfunction "2_2") (pintype "passive"))
      (node (ref "D1") (pin "C") (pinfunction "C_C") (pintype "passive"))
      (node (ref "Q2") (pin "2") (pinfunction "S_2") (pintype "passive"))
      (node (ref "S2") (pin "3") (pinfunction "S_3") (pintype "passive"))
      (node (ref "U$1") (pin "P$1") (pinfunction "1_P$1") (pintype "passive"))
      (node (ref "U$13") (pin "1") (pinfunction "VIN_1") (pintype "bidirectional"))
      (node (ref "U$13") (pin "6") (pinfunction "EN_6") (pintype "bidirectional"))
      (node (ref "U8") (pin "1") (pinfunction "IN_1") (pintype "input"))
    )
    (net (code "60") (name "VUSB") (class "Default")
      (node (ref "C60") (pin "1") (pinfunction "1_1") (pintype "passive"))
      (node (ref "C61") (pin "1") (pinfunction "1_1") (pintype "passive"))
      (node (ref "C64") (pin "1") (pinfunction "1_1") (pintype "passive"))
      (node (ref "D1") (pin "A") (pinfunction "A_A") (pintype "passive"))
      (node (ref "JP7") (pin "1") (pinfunction "VCC_1") (pintype "bidirectional"))
      (node (ref "Q2") (pin "1") (pinfunction "G_1") (pintype "passive"))
      (node (ref "R16") (pin "1") (pinfunction "1_1") (pintype "passive"))
      (node (ref "R23") (pin "2") (pinfunction "2_2") (pintype "passive"))
      (node (ref "U1") (pin "15") (pinfunction "VCC_15") (pintype "bidirectional"))
      (node (ref "U3") (pin "4") (pinfunction "VIN_4") (pintype "power_in"))
    )
    (net (code "61") (name "WS2812") (class "Default")
      (node (ref "IC1") (pin "17") (pinfunction "IO14_17") (pintype "bidirectional"))
      (node (ref "R6") (pin "2") (pinfunction "2_2") (pintype "passive"))
    )
    (net (code "62") (name "unconnected-(IC1A-CAP1_NC-Pad48)") (class "Default")
      (node (ref "IC1") (pin "48") (pinfunction "CAP1_NC_48") (pintype "bidirectional"))
    )
    (net (code "63") (name "unconnected-(IC1A-CAP2_NC-Pad47)") (class "Default")
      (node (ref "IC1") (pin "47") (pinfunction "CAP2_NC_47") (pintype "bidirectional"))
    )
    (net (code "64") (name "unconnected-(IC1A-CLK_DNU-Pad31)") (class "Default")
      (node (ref "IC1") (pin "31") (pinfunction "CLK_DNU_31") (pintype "bidirectional"))
    )
    (net (code "65") (name "unconnected-(IC1A-CMD_DNU-Pad30)") (class "Default")
      (node (ref "IC1") (pin "30") (pinfunction "CMD_DNU_30") (pintype "bidirectional"))
    )
    (net (code "66") (name "unconnected-(IC1A-FLASH_CS_DNU-Pad25)") (class "Default")
      (node (ref "IC1") (pin "25") (pinfunction "FLASH_CS_DNU_25") (pintype "bidirectional"))
    )
    (net (code "67") (name "unconnected-(IC1A-FLASH_SD0_DNU-Pad27)") (class "Default")
      (node (ref "IC1") (pin "27") (pinfunction "FLASH_SD0_DNU_27") (pintype "bidirectional"))
    )
    (net (code "68") (name "unconnected-(IC1A-IO5_DNU-Pad34)") (class "Default")
      (node (ref "IC1") (pin "34") (pinfunction "IO5_DNU_34") (pintype "bidirectional"))
    )
    (net (code "69") (name "unconnected-(IC1A-SD0_DNU-Pad32)") (class "Default")
      (node (ref "IC1") (pin "32") (pinfunction "SD0_DNU_32") (pintype "bidirectional"))
    )
    (net (code "70") (name "unconnected-(IC1A-SD1_DNU-Pad33)") (class "Default")
      (node (ref "IC1") (pin "33") (pinfunction "SD1_DNU_33") (pintype "bidirectional"))
    )
    (net (code "71") (name "unconnected-(IC1A-SD2_DNU-Pad28)") (class "Default")
      (node (ref "IC1") (pin "28") (pinfunction "SD2_DNU_28") (pintype "bidirectional"))
    )
    (net (code "72") (name "unconnected-(IC1A-SD3_DNU-Pad29)") (class "Default")
      (node (ref "IC1") (pin "29") (pinfunction "SD3_DNU_29") (pintype "bidirectional"))
    )
    (net (code "73") (name "unconnected-(IC1A-SENSOR_CAPP-Pad6)") (class "Default")
      (node (ref "IC1") (pin "6") (pinfunction "SENSOR_CAPP_6") (pintype "bidirectional"))
    )
    (net (code "74") (name "unconnected-(IC1A-XTAL_N_NC-Pad44)") (class "Default")
      (node (ref "IC1") (pin "44") (pinfunction "XTAL_N_NC_44") (pintype "bidirectional"))
    )
    (net (code "75") (name "unconnected-(IC1A-XTAL_P_NC-Pad45)") (class "Default")
      (node (ref "IC1") (pin "45") (pinfunction "XTAL_P_NC_45") (pintype "bidirectional"))
    )
    (net (code "76") (name "unconnected-(JP7-ID-Pad4)") (class "Default")
      (node (ref "JP7") (pin "4") (pinfunction "ID_4") (pintype "bidirectional"))
    )
    (net (code "77") (name "unconnected-(LED1-DO-Pad2-DOUT)") (class "Default")
      (node (ref "LED1") (pin "2-DOUT") (pinfunction "DO_2-DOUT") (pintype "output"))
    )
    (net (code "78") (name "unconnected-(SW2-P1-PadA')") (class "Default")
      (node (ref "SW2") (pin "A'") (pinfunction "P1_A'") (pintype "passive"))
    )
    (net (code "79") (name "unconnected-(U$20-DATA1-Pad8)") (class "Default")
      (node (ref "U$20") (pin "8") (pinfunction "DATA1_8") (pintype "bidirectional"))
    )
    (net (code "80") (name "unconnected-(U$20-DATA2-Pad1)") (class "Default")
      (node (ref "U$20") (pin "1") (pinfunction "DATA2_1") (pintype "bidirectional"))
    )
    (net (code "81") (name "unconnected-(U$20-DET-Pad9)") (class "Default")
      (node (ref "U$20") (pin "9") (pinfunction "DET_9") (pintype "bidirectional"))
    )
    (net (code "82") (name "unconnected-(U1-CBUS0-Pad18)") (class "Default")
      (node (ref "U1") (pin "18") (pinfunction "CBUS0_18") (pintype "bidirectional"))
    )
    (net (code "83") (name "unconnected-(U1-CBUS1-Pad17)") (class "Default")
      (node (ref "U1") (pin "17") (pinfunction "CBUS1_17") (pintype "bidirectional"))
    )
    (net (code "84") (name "unconnected-(U1-CBUS2-Pad10)") (class "Default")
      (node (ref "U1") (pin "10") (pinfunction "CBUS2_10") (pintype "bidirectional"))
    )
    (net (code "85") (name "unconnected-(U1-CBUS3-Pad19)") (class "Default")
      (node (ref "U1") (pin "19") (pinfunction "CBUS3_19") (pintype "bidirectional"))
    )
    (net (code "86") (name "unconnected-(U1-~{CTS}-Pad9)") (class "Default")
      (node (ref "U1") (pin "9") (pinfunction "~{CTS}_9") (pintype "bidirectional"))
    )
    (net (code "87") (name "unconnected-(U1-~{DCD}-Pad8)") (class "Default")
      (node (ref "U1") (pin "8") (pinfunction "~{DCD}_8") (pintype "bidirectional"))
    )
    (net (code "88") (name "unconnected-(U1-~{DSR}-Pad7)") (class "Default")
      (node (ref "U1") (pin "7") (pinfunction "~{DSR}_7") (pintype "bidirectional"))
    )
    (net (code "89") (name "unconnected-(U1-~{RI}-Pad5)") (class "Default")
      (node (ref "U1") (pin "5") (pinfunction "~{RI}_5") (pintype "bidirectional"))
    )
    (net (code "90") (name "unconnected-(U8-BP-Pad4)") (class "Default")
      (node (ref "U8") (pin "4") (pinfunction "BP_4") (pintype "input"))
    )
    (net (code "91") (name "~{CS1}") (class "Default")
      (node (ref "IC1") (pin "24") (pinfunction "IO4_24") (pintype "bidirectional"))
      (node (ref "R2") (pin "1") (pinfunction "1_1") (pintype "passive"))
      (node (ref "U$9") (pin "2") (pinfunction "~{CS}_2") (pintype "bidirectional"))
    )
    (net (code "92") (name "~{DRDY}") (class "Default")
      (node (ref "IC1") (pin "10") (pinfunction "I34_10") (pintype "bidirectional"))
      (node (ref "U$9") (pin "14") (pinfunction "~{DRDY}_14") (pintype "bidirectional"))
    )
  )
)
